# Multi_HITSCHIENE_POE.net
KiCad netlist of a schematic drawn in Altium Designer
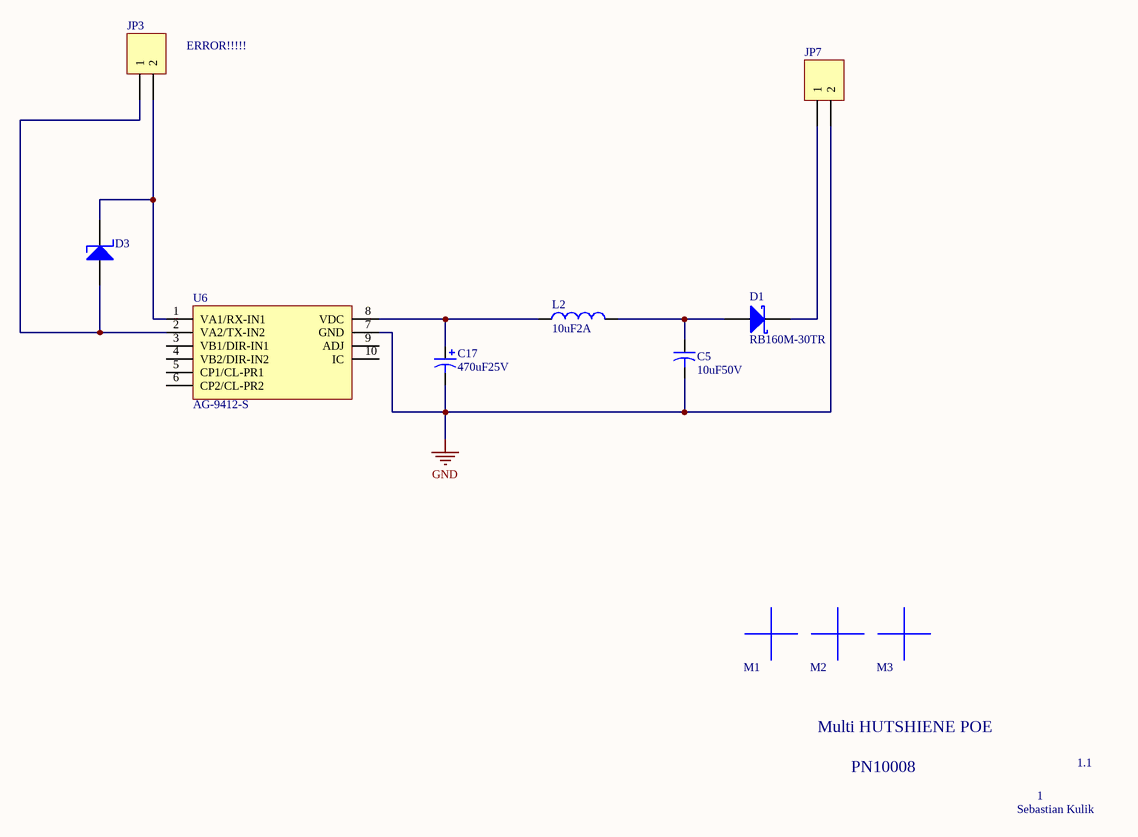
[diagram p0: Multi_HITSCHIENE_POE.SchDoc]

(export (version "E")
  (design (tool "Eeschema 10.0.6"))
  (components
    (comp (ref "C5")
      (value "10uF50V")
      (footprint "C1210")
      (description "AVX,  X7R, 10%, 50V")
      (fields
        (field (name "MANUFACTURER") "AVX")
        (field (name "Comment") "10uF50V_1210")
        (field (name "PUBLISHER") "Sebastian Kulik")
      )
      (libsource (lib "Capacitors") (part "10uF50V_1210"))
    )
    (comp (ref "C17")
      (value "470uF25V")
      (footprint "Panasonic-H13")
      (description "Panasonic, TG series")
      (fields
        (field (name "MANUFACTURER") "Panasonic")
        (field (name "Comment") "470uF25V_POL")
        (field (name "PUBLISHER") "Sebastian Kulik")
      )
      (libsource (lib "Capacitors") (part "470uF25V_POL"))
    )
    (comp (ref "D1")
      (value "RB160M-30TR")
      (footprint "SOD123")
      (description "Diode Schottky,2A,40V")
      (fields (field (name "MANUFACTURER") "Rohm") (field (name "PUBLISHER") "Sebastian Kulik"))
      (libsource (lib "Discrete") (part "RB160M-30TR"))
    )
    (comp (ref "D3")
      (value "SMAJ58A-E3/61")
      (footprint "DO214A")
      (description "TVS, 400W, 58V")
      (fields (field (name "MANUFACTURER") "Vishay") (field (name "PUBLISHER") "Sebastian Kulik"))
      (libsource (lib "Discrete") (part "SMAJ58A-E3/61"))
    )
    (comp (ref "JP3")
      (value "Plug_2_90_2.54")
      (footprint "HDR1X2-SMD")
      (description "Plug, 2-Pin")
      (fields (field (name "MANUFACTURER") "WE") (field (name "PUBLISHER") "Sebastian Kulik"))
      (libsource (lib "Connectors") (part "Plug_2_90_2.54"))
    )
    (comp (ref "JP7")
      (value "Plug_2_90_2.54")
      (footprint "HDR1X2-SMD")
      (description "Plug, 2-Pin")
      (fields (field (name "MANUFACTURER") "WE") (field (name "PUBLISHER") "Sebastian Kulik"))
      (libsource (lib "Connectors") (part "Plug_2_90_2.54"))
    )
    (comp (ref "L2")
      (value "10uF2A")
      (footprint "WE-PD2_1")
      (description "WE-PD2, 10uF2A")
      (fields (field (name "MANUFACTURER") "WE") (field (name "PUBLISHER") "Sebastian Kulik"))
      (libsource (lib "Passives") (part "10uF2A_WE-PD2"))
    )
    (comp (ref "M1") (value "Mark") (footprint "Mark-3mm") (libsource (lib "Symbols") (part "Mark")))
    (comp (ref "M2") (value "Mark") (footprint "Mark-3mm") (libsource (lib "Symbols") (part "Mark")))
    (comp (ref "M3") (value "Mark") (footprint "Mark-3mm") (libsource (lib "Symbols") (part "Mark")))
    (comp (ref "U6")
      (value "AG-9412-S")
      (footprint "AG-9412-S-1")
      (description "PoE, 12V")
      (fields (field (name "MANUFACTURER") "Silvertel") (field (name "PUBLISHER") "Sebastian Kulik"))
      (libsource (lib "ICs") (part "AG-9412-S"))
    )
  )
  (nets
    (net (code "1") (name "GND") (class "Default")
      (node (ref "C17") (pin "2") (pinfunction "2_2") (pintype "passive"))
      (node (ref "C5") (pin "2") (pinfunction "2_2") (pintype "passive"))
      (node (ref "JP7") (pin "2") (pinfunction "2_2") (pintype "passive"))
      (node (ref "U6") (pin "7") (pinfunction "GND_7") (pintype "passive"))
    )
    (net (code "2") (name "Net-(D1-A)") (class "Default")
      (node (ref "C5") (pin "1") (pinfunction "1_1") (pintype "passive"))
      (node (ref "D1") (pin "2") (pinfunction "A_2") (pintype "passive"))
      (node (ref "L2") (pin "2") (pinfunction "2_2") (pintype "passive"))
    )
    (net (code "3") (name "Net-(D1-K)") (class "Default")
      (node (ref "D1") (pin "1") (pinfunction "K_1") (pintype "passive"))
      (node (ref "JP7") (pin "1") (pinfunction "1_1") (pintype "passive"))
    )
    (net (code "4") (name "Net-(D3-A)") (class "Default")
      (node (ref "D3") (pin "2") (pinfunction "A_2") (pintype "passive"))
      (node (ref "JP3") (pin "1") (pinfunction "1_1") (pintype "passive"))
      (node (ref "U6") (pin "2") (pinfunction "VA2/TX-IN2_2") (pintype "passive"))
    )
    (net (code "5") (name "Net-(D3-K)") (class "Default")
      (node (ref "D3") (pin "1") (pinfunction "K_1") (pintype "passive"))
      (node (ref "JP3") (pin "2") (pinfunction "2_2") (pintype "passive"))
      (node (ref "U6") (pin "1") (pinfunction "VA1/RX-IN1_1") (pintype "passive"))
    )
    (net (code "6") (name "Net-(U6-VDC)") (class "Default")
      (node (ref "C17") (pin "1") (pinfunction "1_1") (pintype "passive"))
      (node (ref "L2") (pin "1") (pinfunction "1_1") (pintype "passive"))
      (node (ref "U6") (pin "8") (pinfunction "VDC_8") (pintype "power_in"))
    )
    (net (code "7") (name "unconnected-(U6-ADJ-Pad9)") (class "Default")
      (node (ref "U6") (pin "9") (pinfunction "ADJ_9") (pintype "passive"))
    )
    (net (code "8") (name "unconnected-(U6-CP1{slash}CL-PR1-Pad5)") (class "Default")
      (node (ref "U6") (pin "5") (pinfunction "CP1/CL-PR1_5") (pintype "passive"))
    )
    (net (code "9") (name "unconnected-(U6-CP2{slash}CL-PR2-Pad6)") (class "Default")
      (node (ref "U6") (pin "6") (pinfunction "CP2/CL-PR2_6") (pintype "passive"))
    )
    (net (code "10") (name "unconnected-(U6-IC-Pad10)") (class "Default")
      (node (ref "U6") (pin "10") (pinfunction "IC_10") (pintype "passive"))
    )
    (net (code "11") (name "unconnected-(U6-VB1{slash}DIR-IN1-Pad3)") (class "Default")
      (node (ref "U6") (pin "3") (pinfunction "VB1/DIR-IN1_3") (pintype "passive"))
    )
    (net (code "12") (name "unconnected-(U6-VB2{slash}DIR-IN2-Pad4)") (class "Default")
      (node (ref "U6") (pin "4") (pinfunction "VB2/DIR-IN2_4") (pintype "passive"))
    )
  )
)
